# neopixel_board.net
KiCad netlist of a schematic drawn in EAGLE
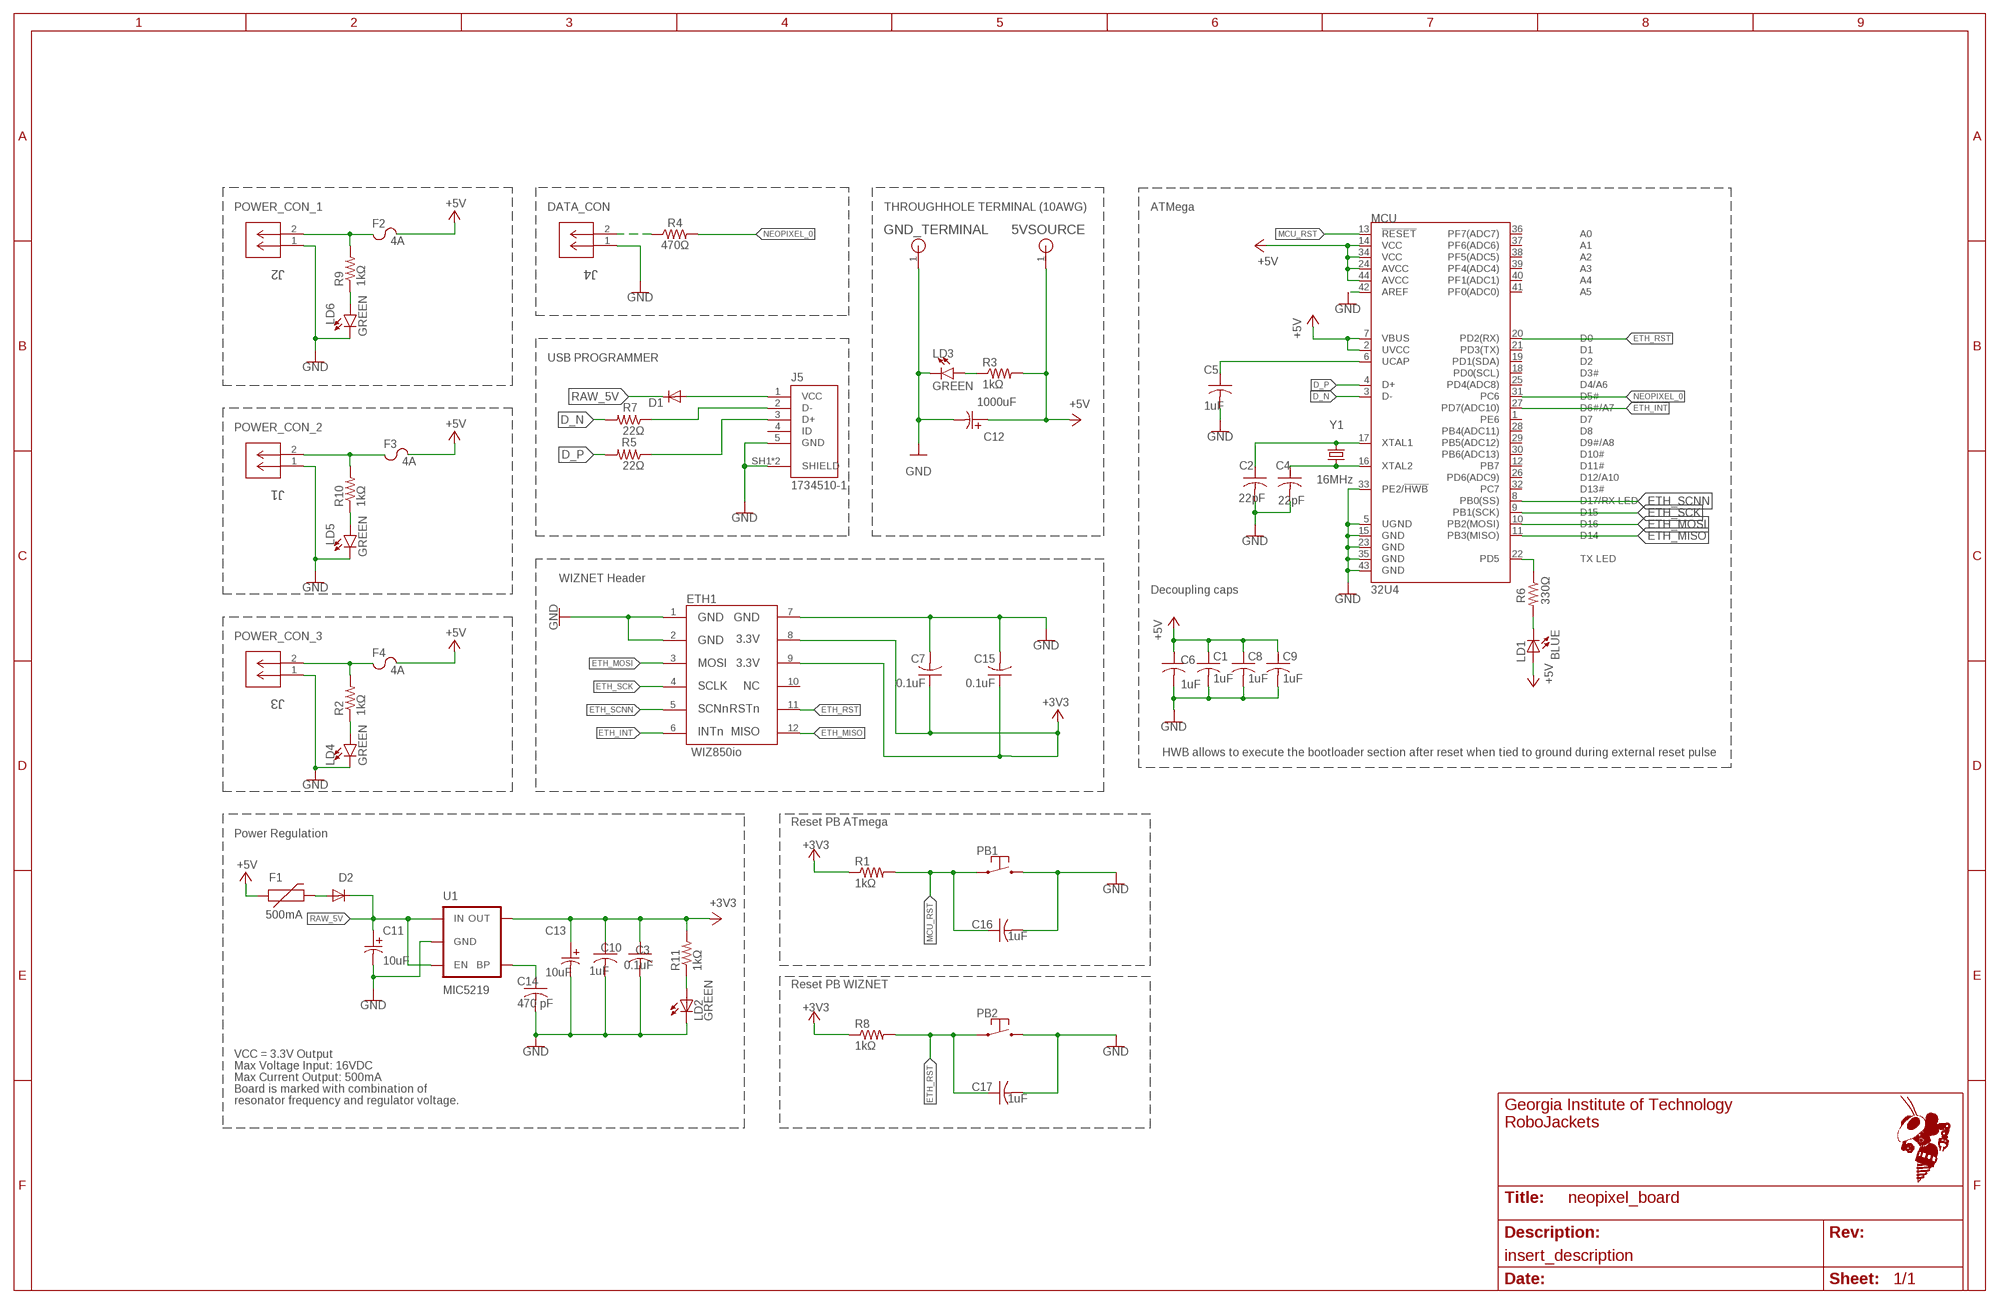
[diagram p0: schematic, sheet 1]

(export (version "E")
  (design (tool "Eeschema 10.0.6"))
  (components
    (comp (ref "5VSOURCE")
      (value "THOLE_SOURCE")
      (footprint "eagle-import:THOLE_SOURCE")
      (libsource (lib "eagle-import") (part "THOLE_SOURCE"))
    )
    (comp (ref "C1")
      (value "1uF")
      (footprint "eagle-import:C0603")
      (libsource (lib "eagle-import") (part "C-USC0603"))
    )
    (comp (ref "C2")
      (value "22pF")
      (footprint "eagle-import:C0603")
      (libsource (lib "eagle-import") (part "C-USC0603"))
    )
    (comp (ref "C3")
      (value "0.1uF")
      (footprint "eagle-import:C0603")
      (libsource (lib "eagle-import") (part "C-USC0603"))
    )
    (comp (ref "C4")
      (value "22pF")
      (footprint "eagle-import:C0603")
      (libsource (lib "eagle-import") (part "C-USC0603"))
    )
    (comp (ref "C5")
      (value "1uF")
      (footprint "eagle-import:C0603")
      (libsource (lib "eagle-import") (part "C-USC0603"))
    )
    (comp (ref "C6")
      (value "1uF")
      (footprint "eagle-import:C0603")
      (libsource (lib "eagle-import") (part "C-USC0603"))
    )
    (comp (ref "C7")
      (value "0.1uF")
      (footprint "eagle-import:C0603")
      (fields (field (name "SPICEPREFIX") "0.1 uF"))
      (libsource (lib "eagle-import") (part "C-USC0603"))
    )
    (comp (ref "C8")
      (value "1uF")
      (footprint "eagle-import:C0603")
      (libsource (lib "eagle-import") (part "C-USC0603"))
    )
    (comp (ref "C9")
      (value "1uF")
      (footprint "eagle-import:C0603")
      (libsource (lib "eagle-import") (part "C-USC0603"))
    )
    (comp (ref "C10")
      (value "1uF")
      (footprint "eagle-import:C0603")
      (libsource (lib "eagle-import") (part "C-USC0603"))
    )
    (comp (ref "C11")
      (value "10uF")
      (footprint "eagle-import:CAP_4_X_5.4")
      (libsource (lib "eagle-import") (part "EEE-1CA100SR"))
    )
    (comp (ref "C12")
      (value "1000uF")
      (footprint "eagle-import:PCAP_8X112")
      (fields (field (name "MANUFACTURER_PART_NUMBER") "ECA0JM102"))
      (libsource (lib "eagle-import") (part "ECA-0JM102"))
    )
    (comp (ref "C13")
      (value "10uF")
      (footprint "eagle-import:CAP_4_X_5.4")
      (libsource (lib "eagle-import") (part "EEE-1CA100SR"))
    )
    (comp (ref "C14")
      (value "470 pF")
      (footprint "eagle-import:C0603")
      (fields (field (name "SPICEPREFIX") "0.1 uF"))
      (libsource (lib "eagle-import") (part "C-USC0603"))
    )
    (comp (ref "C15")
      (value "0.1uF")
      (footprint "eagle-import:C0603")
      (fields (field (name "SPICEPREFIX") "0.1 uF"))
      (libsource (lib "eagle-import") (part "C-USC0603"))
    )
    (comp (ref "C16")
      (value "1uF")
      (footprint "eagle-import:C0603")
      (libsource (lib "eagle-import") (part "C-USC0603"))
    )
    (comp (ref "C17")
      (value "1uF")
      (footprint "eagle-import:C0603")
      (libsource (lib "eagle-import") (part "C-USC0603"))
    )
    (comp (ref "D1")
      (value "DIODESOD")
      (footprint "eagle-import:SOD-323")
      (libsource (lib "eagle-import") (part "DIODESOD"))
    )
    (comp (ref "D2")
      (value "DIODESOD")
      (footprint "eagle-import:SOD-323")
      (libsource (lib "eagle-import") (part "DIODESOD"))
    )
    (comp (ref "ETH1")
      (value "WIZ850IO")
      (footprint "eagle-import:WIZ850IO")
      (libsource (lib "eagle-import") (part "WIZ850IO"))
    )
    (comp (ref "F1")
      (value "500mA")
      (footprint "eagle-import:PTC-1206")
      (libsource (lib "eagle-import") (part "PTCSMD"))
    )
    (comp (ref "F2")
      (value "4A")
      (footprint "eagle-import:3557-2")
      (fields (field (name "MPN") "3557-2"))
      (libsource (lib "eagle-import") (part "3557-2"))
    )
    (comp (ref "F3")
      (value "4A")
      (footprint "eagle-import:3557-2")
      (fields (field (name "MPN") "3557-2"))
      (libsource (lib "eagle-import") (part "3557-2"))
    )
    (comp (ref "F4")
      (value "4A")
      (footprint "eagle-import:3557-2")
      (fields (field (name "MPN") "3557-2"))
      (libsource (lib "eagle-import") (part "3557-2"))
    )
    (comp (ref "GND_TERMINAL")
      (value "THOLE_SOURCE")
      (footprint "eagle-import:THOLE_SOURCE")
      (libsource (lib "eagle-import") (part "THOLE_SOURCE"))
    )
    (comp (ref "J1")
      (value "SSW-102-02-T-S-RA")
      (footprint "eagle-import:CON2_1X2_TR_SSQ")
      (fields (field (name "MANUFACTURER_PART_NUMBER") "SSW10202TSRA"))
      (libsource (lib "eagle-import") (part "SSW-102-02-T-S-RA"))
    )
    (comp (ref "J2")
      (value "SSW-102-02-T-S-RA")
      (footprint "eagle-import:CON2_1X2_TR_SSQ")
      (fields (field (name "MANUFACTURER_PART_NUMBER") "SSW10202TSRA"))
      (libsource (lib "eagle-import") (part "SSW-102-02-T-S-RA"))
    )
    (comp (ref "J3")
      (value "SSW-102-02-T-S-RA")
      (footprint "eagle-import:CON2_1X2_TR_SSQ")
      (fields (field (name "MANUFACTURER_PART_NUMBER") "SSW10202TSRA"))
      (libsource (lib "eagle-import") (part "SSW-102-02-T-S-RA"))
    )
    (comp (ref "J4")
      (value "SSW-102-02-T-S-RA")
      (footprint "eagle-import:CON2_1X2_TR_SSQ")
      (fields (field (name "MANUFACTURER_PART_NUMBER") "SSW10202TSRA"))
      (libsource (lib "eagle-import") (part "SSW-102-02-T-S-RA"))
    )
    (comp (ref "J5")
      (value "1734510-1")
      (footprint "eagle-import:TE_1734510-1")
      (fields (field (name "MANUFACTURER") "TE Connectivity"))
      (libsource (lib "eagle-import") (part "1734510-1"))
    )
    (comp (ref "LD1")
      (value "BLUE")
      (footprint "eagle-import:LED-0603")
      (libsource (lib "eagle-import") (part "LED0603"))
    )
    (comp (ref "LD2")
      (value "GREEN")
      (footprint "eagle-import:LED-0603")
      (libsource (lib "eagle-import") (part "LED0603"))
    )
    (comp (ref "LD3")
      (value "GREEN")
      (footprint "eagle-import:LED-0603")
      (libsource (lib "eagle-import") (part "LED-GREEN0603"))
    )
    (comp (ref "LD4")
      (value "GREEN")
      (footprint "eagle-import:LED-0603")
      (libsource (lib "eagle-import") (part "LED-GREEN0603"))
    )
    (comp (ref "LD5")
      (value "GREEN")
      (footprint "eagle-import:LED-0603")
      (libsource (lib "eagle-import") (part "LED-GREEN0603"))
    )
    (comp (ref "LD6")
      (value "GREEN")
      (footprint "eagle-import:LED-0603")
      (libsource (lib "eagle-import") (part "LED-GREEN0603"))
    )
    (comp (ref "MCU")
      (value "32U4")
      (footprint "eagle-import:TQFP44")
      (libsource (lib "eagle-import") (part "ATMEGA32U4TQFP-44"))
    )
    (comp (ref "PB1")
      (value "PTS645PTS645_SMD1")
      (footprint "eagle-import:PTS645_SMD")
      (libsource (lib "eagle-import") (part "PTS645PTS645_SMD1"))
    )
    (comp (ref "PB2")
      (value "PTS645PTS645_SMD1")
      (footprint "eagle-import:PTS645_SMD")
      (libsource (lib "eagle-import") (part "PTS645PTS645_SMD1"))
    )
    (comp (ref "R1")
      (value "1kΩ")
      (footprint "eagle-import:R0603")
      (libsource (lib "eagle-import") (part "R-US_R0603"))
    )
    (comp (ref "R2")
      (value "1kΩ")
      (footprint "eagle-import:0603-RES")
      (libsource (lib "eagle-import") (part "RESISTOR0603-RES"))
    )
    (comp (ref "R3")
      (value "1kΩ")
      (footprint "eagle-import:0603-RES")
      (libsource (lib "eagle-import") (part "RESISTOR0603-RES"))
    )
    (comp (ref "R4")
      (value "470Ω")
      (footprint "eagle-import:0603")
      (libsource (lib "eagle-import") (part "470OHM-0603-1/10W-1%"))
    )
    (comp (ref "R5")
      (value "22Ω")
      (footprint "eagle-import:0603-RES")
      (libsource (lib "eagle-import") (part "RESISTOR0603-RES"))
    )
    (comp (ref "R6")
      (value "330Ω")
      (footprint "eagle-import:0603-RES")
      (libsource (lib "eagle-import") (part "RESISTOR0603-RES"))
    )
    (comp (ref "R7")
      (value "22Ω")
      (footprint "eagle-import:0603-RES")
      (libsource (lib "eagle-import") (part "RESISTOR0603-RES"))
    )
    (comp (ref "R8")
      (value "1kΩ")
      (footprint "eagle-import:R0603")
      (libsource (lib "eagle-import") (part "R-US_R0603"))
    )
    (comp (ref "R9")
      (value "1kΩ")
      (footprint "eagle-import:0603-RES")
      (libsource (lib "eagle-import") (part "RESISTOR0603-RES"))
    )
    (comp (ref "R10")
      (value "1kΩ")
      (footprint "eagle-import:0603-RES")
      (libsource (lib "eagle-import") (part "RESISTOR0603-RES"))
    )
    (comp (ref "R11")
      (value "1kΩ")
      (footprint "eagle-import:0603-RES")
      (libsource (lib "eagle-import") (part "RESISTOR0603-RES"))
    )
    (comp (ref "U1")
      (value "MIC5219")
      (footprint "eagle-import:SOT23-5")
      (libsource (lib "eagle-import") (part "V_REG_LDOSMD"))
    )
    (comp (ref "Y1")
      (value "16MHz")
      (footprint "eagle-import:CRYSTAL-SMD-5X3")
      (libsource (lib "eagle-import") (part "CRYSTAL5X3"))
    )
  )
  (nets
    (net (code "1") (name "+3V3") (class "Default")
      (node (ref "C10") (pin "1") (pinfunction "1_1") (pintype "passive"))
      (node (ref "C13") (pin "1") (pinfunction "11_1") (pintype "passive"))
      (node (ref "C15") (pin "1") (pinfunction "1_1") (pintype "passive"))
      (node (ref "C3") (pin "1") (pinfunction "1_1") (pintype "passive"))
      (node (ref "C7") (pin "1") (pinfunction "1_1") (pintype "passive"))
      (node (ref "ETH1") (pin "8") (pinfunction "8_8") (pintype "bidirectional"))
      (node (ref "ETH1") (pin "9") (pinfunction "9_9") (pintype "bidirectional"))
      (node (ref "R1") (pin "1") (pinfunction "1_1") (pintype "passive"))
      (node (ref "R11") (pin "2") (pinfunction "2_2") (pintype "passive"))
      (node (ref "R8") (pin "1") (pinfunction "1_1") (pintype "passive"))
      (node (ref "U1") (pin "5") (pinfunction "OUT_5") (pintype "passive"))
    )
    (net (code "2") (name "+5V") (class "Default")
      (node (ref "5VSOURCE") (pin "1") (pinfunction "1_1") (pintype "passive"))
      (node (ref "C1") (pin "1") (pinfunction "1_1") (pintype "passive"))
      (node (ref "C12") (pin "1") (pinfunction "11_1") (pintype "passive"))
      (node (ref "C6") (pin "1") (pinfunction "1_1") (pintype "passive"))
      (node (ref "C8") (pin "1") (pinfunction "1_1") (pintype "passive"))
      (node (ref "C9") (pin "1") (pinfunction "1_1") (pintype "passive"))
      (node (ref "F1") (pin "1") (pinfunction "1_1") (pintype "bidirectional"))
      (node (ref "F2") (pin "3") (pinfunction "2_3") (pintype "bidirectional"))
      (node (ref "F2") (pin "4") (pinfunction "2_4") (pintype "bidirectional"))
      (node (ref "F3") (pin "3") (pinfunction "2_3") (pintype "bidirectional"))
      (node (ref "F3") (pin "4") (pinfunction "2_4") (pintype "bidirectional"))
      (node (ref "F4") (pin "3") (pinfunction "2_3") (pintype "bidirectional"))
      (node (ref "F4") (pin "4") (pinfunction "2_4") (pintype "bidirectional"))
      (node (ref "LD1") (pin "A") (pinfunction "A_A") (pintype "passive"))
      (node (ref "MCU") (pin "14") (pinfunction "VCC_14") (pintype "bidirectional"))
      (node (ref "MCU") (pin "2") (pinfunction "UVCC_2") (pintype "bidirectional"))
      (node (ref "MCU") (pin "24") (pinfunction "AVCC_24") (pintype "bidirectional"))
      (node (ref "MCU") (pin "34") (pinfunction "VCC_34") (pintype "bidirectional"))
      (node (ref "MCU") (pin "44") (pinfunction "AVCC_44") (pintype "bidirectional"))
      (node (ref "MCU") (pin "7") (pinfunction "VBUS_7") (pintype "bidirectional"))
      (node (ref "R3") (pin "2") (pinfunction "2_2") (pintype "passive"))
    )
    (net (code "3") (name "D_N") (class "Default")
      (node (ref "MCU") (pin "3") (pinfunction "D-_3") (pintype "bidirectional"))
      (node (ref "R7") (pin "2") (pinfunction "2_2") (pintype "passive"))
    )
    (net (code "4") (name "D_P") (class "Default")
      (node (ref "MCU") (pin "4") (pinfunction "D+_4") (pintype "bidirectional"))
      (node (ref "R5") (pin "2") (pinfunction "2_2") (pintype "passive"))
    )
    (net (code "5") (name "ETH_INT") (class "Default")
      (node (ref "ETH1") (pin "6") (pinfunction "6_6") (pintype "bidirectional"))
      (node (ref "MCU") (pin "27") (pinfunction "PD7(ADC10)_27") (pintype "bidirectional"))
    )
    (net (code "6") (name "ETH_MISO") (class "Default")
      (node (ref "ETH1") (pin "12") (pinfunction "12_12") (pintype "bidirectional"))
      (node (ref "MCU") (pin "11") (pinfunction "PB3(MISO)_11") (pintype "bidirectional"))
    )
    (net (code "7") (name "ETH_MOSI") (class "Default")
      (node (ref "ETH1") (pin "3") (pinfunction "3_3") (pintype "bidirectional"))
      (node (ref "MCU") (pin "10") (pinfunction "PB2(MOSI)_10") (pintype "bidirectional"))
    )
    (net (code "8") (name "ETH_RST") (class "Default")
      (node (ref "C17") (pin "1") (pinfunction "1_1") (pintype "passive"))
      (node (ref "ETH1") (pin "11") (pinfunction "11_11") (pintype "bidirectional"))
      (node (ref "MCU") (pin "20") (pinfunction "PD2(RX)_20") (pintype "bidirectional"))
      (node (ref "PB2") (pin "P$1") (pinfunction "1_P$1") (pintype "passive"))
      (node (ref "PB2") (pin "P$2") (pinfunction "1_P$2") (pintype "passive"))
      (node (ref "R8") (pin "2") (pinfunction "2_2") (pintype "passive"))
    )
    (net (code "9") (name "ETH_SCK") (class "Default")
      (node (ref "ETH1") (pin "4") (pinfunction "4_4") (pintype "bidirectional"))
      (node (ref "MCU") (pin "9") (pinfunction "PB1(SCK)_9") (pintype "bidirectional"))
    )
    (net (code "10") (name "ETH_SCNN") (class "Default")
      (node (ref "ETH1") (pin "5") (pinfunction "5_5") (pintype "bidirectional"))
      (node (ref "MCU") (pin "8") (pinfunction "PB0(SS)_8") (pintype "bidirectional"))
    )
    (net (code "11") (name "GND") (class "Default")
      (node (ref "C1") (pin "2") (pinfunction "2_2") (pintype "passive"))
      (node (ref "C10") (pin "2") (pinfunction "2_2") (pintype "passive"))
      (node (ref "C11") (pin "2") (pinfunction "22_2") (pintype "passive"))
      (node (ref "C12") (pin "2") (pinfunction "22_2") (pintype "passive"))
      (node (ref "C13") (pin "2") (pinfunction "22_2") (pintype "passive"))
      (node (ref "C14") (pin "2") (pinfunction "2_2") (pintype "passive"))
      (node (ref "C15") (pin "2") (pinfunction "2_2") (pintype "passive"))
      (node (ref "C16") (pin "2") (pinfunction "2_2") (pintype "passive"))
      (node (ref "C17") (pin "2") (pinfunction "2_2") (pintype "passive"))
      (node (ref "C2") (pin "2") (pinfunction "2_2") (pintype "passive"))
      (node (ref "C3") (pin "2") (pinfunction "2_2") (pintype "passive"))
      (node (ref "C4") (pin "2") (pinfunction "2_2") (pintype "passive"))
      (node (ref "C5") (pin "2") (pinfunction "2_2") (pintype "passive"))
      (node (ref "C6") (pin "2") (pinfunction "2_2") (pintype "passive"))
      (node (ref "C7") (pin "2") (pinfunction "2_2") (pintype "passive"))
      (node (ref "C8") (pin "2") (pinfunction "2_2") (pintype "passive"))
      (node (ref "C9") (pin "2") (pinfunction "2_2") (pintype "passive"))
      (node (ref "ETH1") (pin "1") (pinfunction "1_1") (pintype "bidirectional"))
      (node (ref "ETH1") (pin "2") (pinfunction "2_2") (pintype "bidirectional"))
      (node (ref "ETH1") (pin "7") (pinfunction "7_7") (pintype "bidirectional"))
      (node (ref "GND_TERMINAL") (pin "1") (pinfunction "1_1") (pintype "passive"))
      (node (ref "J1") (pin "1") (pinfunction "1_1") (pintype "passive"))
      (node (ref "J2") (pin "1") (pinfunction "1_1") (pintype "passive"))
      (node (ref "J3") (pin "1") (pinfunction "1_1") (pintype "passive"))
      (node (ref "J4") (pin "1") (pinfunction "1_1") (pintype "passive"))
      (node (ref "J5") (pin "5") (pinfunction "GND_5") (pintype "passive"))
      (node (ref "J5") (pin "SH1") (pinfunction "SHIELD_SH1") (pintype "passive"))
      (node (ref "J5") (pin "SH2") (pinfunction "SHIELD_SH2") (pintype "passive"))
      (node (ref "LD2") (pin "C") (pinfunction "C_C") (pintype "passive"))
      (node (ref "LD3") (pin "C") (pinfunction "C_C") (pintype "passive"))
      (node (ref "LD4") (pin "C") (pinfunction "C_C") (pintype "passive"))
      (node (ref "LD5") (pin "C") (pinfunction "C_C") (pintype "passive"))
      (node (ref "LD6") (pin "C") (pinfunction "C_C") (pintype "passive"))
      (node (ref "MCU") (pin "15") (pinfunction "GND_15") (pintype "bidirectional"))
      (node (ref "MCU") (pin "23") (pinfunction "GND_23") (pintype "bidirectional"))
      (node (ref "MCU") (pin "33") (pinfunction "PE2/~{HWB}_33") (pintype "bidirectional"))
      (node (ref "MCU") (pin "35") (pinfunction "GND_35") (pintype "bidirectional"))
      (node (ref "MCU") (pin "42") (pinfunction "AREF_42") (pintype "bidirectional"))
      (node (ref "MCU") (pin "43") (pinfunction "GND_43") (pintype "bidirectional"))
      (node (ref "MCU") (pin "5") (pinfunction "UGND_5") (pintype "bidirectional"))
      (node (ref "PB1") (pin "P$3") (pinfunction "2_P$3") (pintype "passive"))
      (node (ref "PB1") (pin "P$4") (pinfunction "2_P$4") (pintype "passive"))
      (node (ref "PB2") (pin "P$3") (pinfunction "2_P$3") (pintype "passive"))
      (node (ref "PB2") (pin "P$4") (pinfunction "2_P$4") (pintype "passive"))
      (node (ref "U1") (pin "2") (pinfunction "GND_2") (pintype "input"))
    )
    (net (code "12") (name "MCU_RST") (class "Default")
      (node (ref "C16") (pin "1") (pinfunction "1_1") (pintype "passive"))
      (node (ref "MCU") (pin "13") (pinfunction "~{RESET}_13") (pintype "bidirectional"))
      (node (ref "PB1") (pin "P$1") (pinfunction "1_P$1") (pintype "passive"))
      (node (ref "PB1") (pin "P$2") (pinfunction "1_P$2") (pintype "passive"))
      (node (ref "R1") (pin "2") (pinfunction "2_2") (pintype "passive"))
    )
    (net (code "13") (name "NEOPIXEL_0") (class "Default")
      (node (ref "MCU") (pin "31") (pinfunction "PC6_31") (pintype "bidirectional"))
      (node (ref "R4") (pin "2") (pinfunction "2_2") (pintype "passive"))
    )
    (net (code "14") (name "Net-(D1-A)") (class "Default")
      (node (ref "D1") (pin "2") (pinfunction "A_2") (pintype "passive"))
      (node (ref "J5") (pin "1") (pinfunction "VCC_1") (pintype "passive"))
    )
    (net (code "15") (name "Net-(D2-A)") (class "Default")
      (node (ref "D2") (pin "2") (pinfunction "A_2") (pintype "passive"))
      (node (ref "F1") (pin "2") (pinfunction "2_2") (pintype "bidirectional"))
    )
    (net (code "16") (name "Net-(F2-1-Pad2)") (class "Default")
      (node (ref "F2") (pin "1") (pinfunction "1_1") (pintype "bidirectional"))
      (node (ref "F2") (pin "2") (pinfunction "1_2") (pintype "bidirectional"))
      (node (ref "J2") (pin "2") (pinfunction "2_2") (pintype "passive"))
      (node (ref "R9") (pin "2") (pinfunction "2_2") (pintype "passive"))
    )
    (net (code "17") (name "Net-(F3-1-Pad2)") (class "Default")
      (node (ref "F3") (pin "1") (pinfunction "1_1") (pintype "bidirectional"))
      (node (ref "F3") (pin "2") (pinfunction "1_2") (pintype "bidirectional"))
      (node (ref "J1") (pin "2") (pinfunction "2_2") (pintype "passive"))
      (node (ref "R10") (pin "2") (pinfunction "2_2") (pintype "passive"))
    )
    (net (code "18") (name "Net-(F4-1-Pad2)") (class "Default")
      (node (ref "F4") (pin "1") (pinfunction "1_1") (pintype "bidirectional"))
      (node (ref "F4") (pin "2") (pinfunction "1_2") (pintype "bidirectional"))
      (node (ref "J3") (pin "2") (pinfunction "2_2") (pintype "passive"))
      (node (ref "R2") (pin "2") (pinfunction "2_2") (pintype "passive"))
    )
    (net (code "19") (name "Net-(J4-Pad2)") (class "Default")
      (node (ref "J4") (pin "2") (pinfunction "2_2") (pintype "passive"))
      (node (ref "R4") (pin "1") (pinfunction "1_1") (pintype "passive"))
    )
    (net (code "20") (name "Net-(J5-D+)") (class "Default")
      (node (ref "J5") (pin "3") (pinfunction "D+_3") (pintype "passive"))
      (node (ref "R5") (pin "1") (pinfunction "1_1") (pintype "passive"))
    )
    (net (code "21") (name "Net-(J5-D-)") (class "Default")
      (node (ref "J5") (pin "2") (pinfunction "D-_2") (pintype "passive"))
      (node (ref "R7") (pin "1") (pinfunction "1_1") (pintype "passive"))
    )
    (net (code "22") (name "Net-(LD1-PadC)") (class "Default")
      (node (ref "LD1") (pin "C") (pinfunction "C_C") (pintype "passive"))
      (node (ref "R6") (pin "2") (pinfunction "2_2") (pintype "passive"))
    )
    (net (code "23") (name "Net-(LD2-PadA)") (class "Default")
      (node (ref "LD2") (pin "A") (pinfunction "A_A") (pintype "passive"))
      (node (ref "R11") (pin "1") (pinfunction "1_1") (pintype "passive"))
    )
    (net (code "24") (name "Net-(LD3-PadA)") (class "Default")
      (node (ref "LD3") (pin "A") (pinfunction "A_A") (pintype "passive"))
      (node (ref "R3") (pin "1") (pinfunction "1_1") (pintype "passive"))
    )
    (net (code "25") (name "Net-(LD4-PadA)") (class "Default")
      (node (ref "LD4") (pin "A") (pinfunction "A_A") (pintype "passive"))
      (node (ref "R2") (pin "1") (pinfunction "1_1") (pintype "passive"))
    )
    (net (code "26") (name "Net-(LD5-PadA)") (class "Default")
      (node (ref "LD5") (pin "A") (pinfunction "A_A") (pintype "passive"))
      (node (ref "R10") (pin "1") (pinfunction "1_1") (pintype "passive"))
    )
    (net (code "27") (name "Net-(LD6-PadA)") (class "Default")
      (node (ref "LD6") (pin "A") (pinfunction "A_A") (pintype "passive"))
      (node (ref "R9") (pin "1") (pinfunction "1_1") (pintype "passive"))
    )
    (net (code "28") (name "Net-(MCU-PD5)") (class "Default")
      (node (ref "MCU") (pin "22") (pinfunction "PD5_22") (pintype "bidirectional"))
      (node (ref "R6") (pin "1") (pinfunction "1_1") (pintype "passive"))
    )
    (net (code "29") (name "Net-(MCU-UCAP)") (class "Default")
      (node (ref "C5") (pin "1") (pinfunction "1_1") (pintype "passive"))
      (node (ref "MCU") (pin "6") (pinfunction "UCAP_6") (pintype "bidirectional"))
    )
    (net (code "30") (name "Net-(MCU-XTAL1)") (class "Default")
      (node (ref "C2") (pin "1") (pinfunction "1_1") (pintype "passive"))
      (node (ref "MCU") (pin "17") (pinfunction "XTAL1_17") (pintype "bidirectional"))
      (node (ref "Y1") (pin "3") (pinfunction "2_3") (pintype "passive"))
    )
    (net (code "31") (name "Net-(MCU-XTAL2)") (class "Default")
      (node (ref "C4") (pin "1") (pinfunction "1_1") (pintype "passive"))
      (node (ref "MCU") (pin "16") (pinfunction "XTAL2_16") (pintype "bidirectional"))
      (node (ref "Y1") (pin "1") (pinfunction "1_1") (pintype "passive"))
    )
    (net (code "32") (name "Net-(U1-BP)") (class "Default")
      (node (ref "C14") (pin "1") (pinfunction "1_1") (pintype "passive"))
      (node (ref "U1") (pin "4") (pinfunction "BP_4") (pintype "input"))
    )
    (net (code "33") (name "RAW_5V") (class "Default")
      (node (ref "C11") (pin "1") (pinfunction "11_1") (pintype "passive"))
      (node (ref "D1") (pin "1") (pinfunction "C_1") (pintype "passive"))
      (node (ref "D2") (pin "1") (pinfunction "C_1") (pintype "passive"))
      (node (ref "U1") (pin "1") (pinfunction "IN_1") (pintype "input"))
      (node (ref "U1") (pin "3") (pinfunction "EN_3") (pintype "input"))
    )
    (net (code "34") (name "unconnected-(ETH1-Pad10)") (class "Default")
      (node (ref "ETH1") (pin "10") (pinfunction "10_10") (pintype "bidirectional"))
    )
    (net (code "35") (name "unconnected-(J5-ID-Pad4)") (class "Default")
      (node (ref "J5") (pin "4") (pinfunction "ID_4") (pintype "passive"))
    )
    (net (code "36") (name "unconnected-(MCU-PB4(ADC11)-Pad28)") (class "Default")
      (node (ref "MCU") (pin "28") (pinfunction "PB4(ADC11)_28") (pintype "bidirectional"))
    )
    (net (code "37") (name "unconnected-(MCU-PB5(ADC12)-Pad29)") (class "Default")
      (node (ref "MCU") (pin "29") (pinfunction "PB5(ADC12)_29") (pintype "bidirectional"))
    )
    (net (code "38") (name "unconnected-(MCU-PB6(ADC13)-Pad30)") (class "Default")
      (node (ref "MCU") (pin "30") (pinfunction "PB6(ADC13)_30") (pintype "bidirectional"))
    )
    (net (code "39") (name "unconnected-(MCU-PB7-Pad12)") (class "Default")
      (node (ref "MCU") (pin "12") (pinfunction "PB7_12") (pintype "bidirectional"))
    )
    (net (code "40") (name "unconnected-(MCU-PC7-Pad32)") (class "Default")
      (node (ref "MCU") (pin "32") (pinfunction "PC7_32") (pintype "bidirectional"))
    )
    (net (code "41") (name "unconnected-(MCU-PD0(SCL)-Pad18)") (class "Default")
      (node (ref "MCU") (pin "18") (pinfunction "PD0(SCL)_18") (pintype "bidirectional"))
    )
    (net (code "42") (name "unconnected-(MCU-PD1(SDA)-Pad19)") (class "Default")
      (node (ref "MCU") (pin "19") (pinfunction "PD1(SDA)_19") (pintype "bidirectional"))
    )
    (net (code "43") (name "unconnected-(MCU-PD3(TX)-Pad21)") (class "Default")
      (node (ref "MCU") (pin "21") (pinfunction "PD3(TX)_21") (pintype "bidirectional"))
    )
    (net (code "44") (name "unconnected-(MCU-PD4(ADC8)-Pad25)") (class "Default")
      (node (ref "MCU") (pin "25") (pinfunction "PD4(ADC8)_25") (pintype "bidirectional"))
    )
    (net (code "45") (name "unconnected-(MCU-PD6(ADC9)-Pad26)") (class "Default")
      (node (ref "MCU") (pin "26") (pinfunction "PD6(ADC9)_26") (pintype "bidirectional"))
    )
    (net (code "46") (name "unconnected-(MCU-PE6-Pad1)") (class "Default")
      (node (ref "MCU") (pin "1") (pinfunction "PE6_1") (pintype "bidirectional"))
    )
    (net (code "47") (name "unconnected-(MCU-PF0(ADC0)-Pad41)") (class "Default")
      (node (ref "MCU") (pin "41") (pinfunction "PF0(ADC0)_41") (pintype "bidirectional"))
    )
    (net (code "48") (name "unconnected-(MCU-PF1(ADC1)-Pad40)") (class "Default")
      (node (ref "MCU") (pin "40") (pinfunction "PF1(ADC1)_40") (pintype "bidirectional"))
    )
    (net (code "49") (name "unconnected-(MCU-PF4(ADC4)-Pad39)") (class "Default")
      (node (ref "MCU") (pin "39") (pinfunction "PF4(ADC4)_39") (pintype "bidirectional"))
    )
    (net (code "50") (name "unconnected-(MCU-PF5(ADC5)-Pad38)") (class "Default")
      (node (ref "MCU") (pin "38") (pinfunction "PF5(ADC5)_38") (pintype "bidirectional"))
    )
    (net (code "51") (name "unconnected-(MCU-PF6(ADC6)-Pad37)") (class "Default")
      (node (ref "MCU") (pin "37") (pinfunction "PF6(ADC6)_37") (pintype "bidirectional"))
    )
    (net (code "52") (name "unconnected-(MCU-PF7(ADC7)-Pad36)") (class "Default")
      (node (ref "MCU") (pin "36") (pinfunction "PF7(ADC7)_36") (pintype "bidirectional"))
    )
  )
)
